# trinamic-controller.net
KiCad netlist of a schematic drawn in Altium Designer
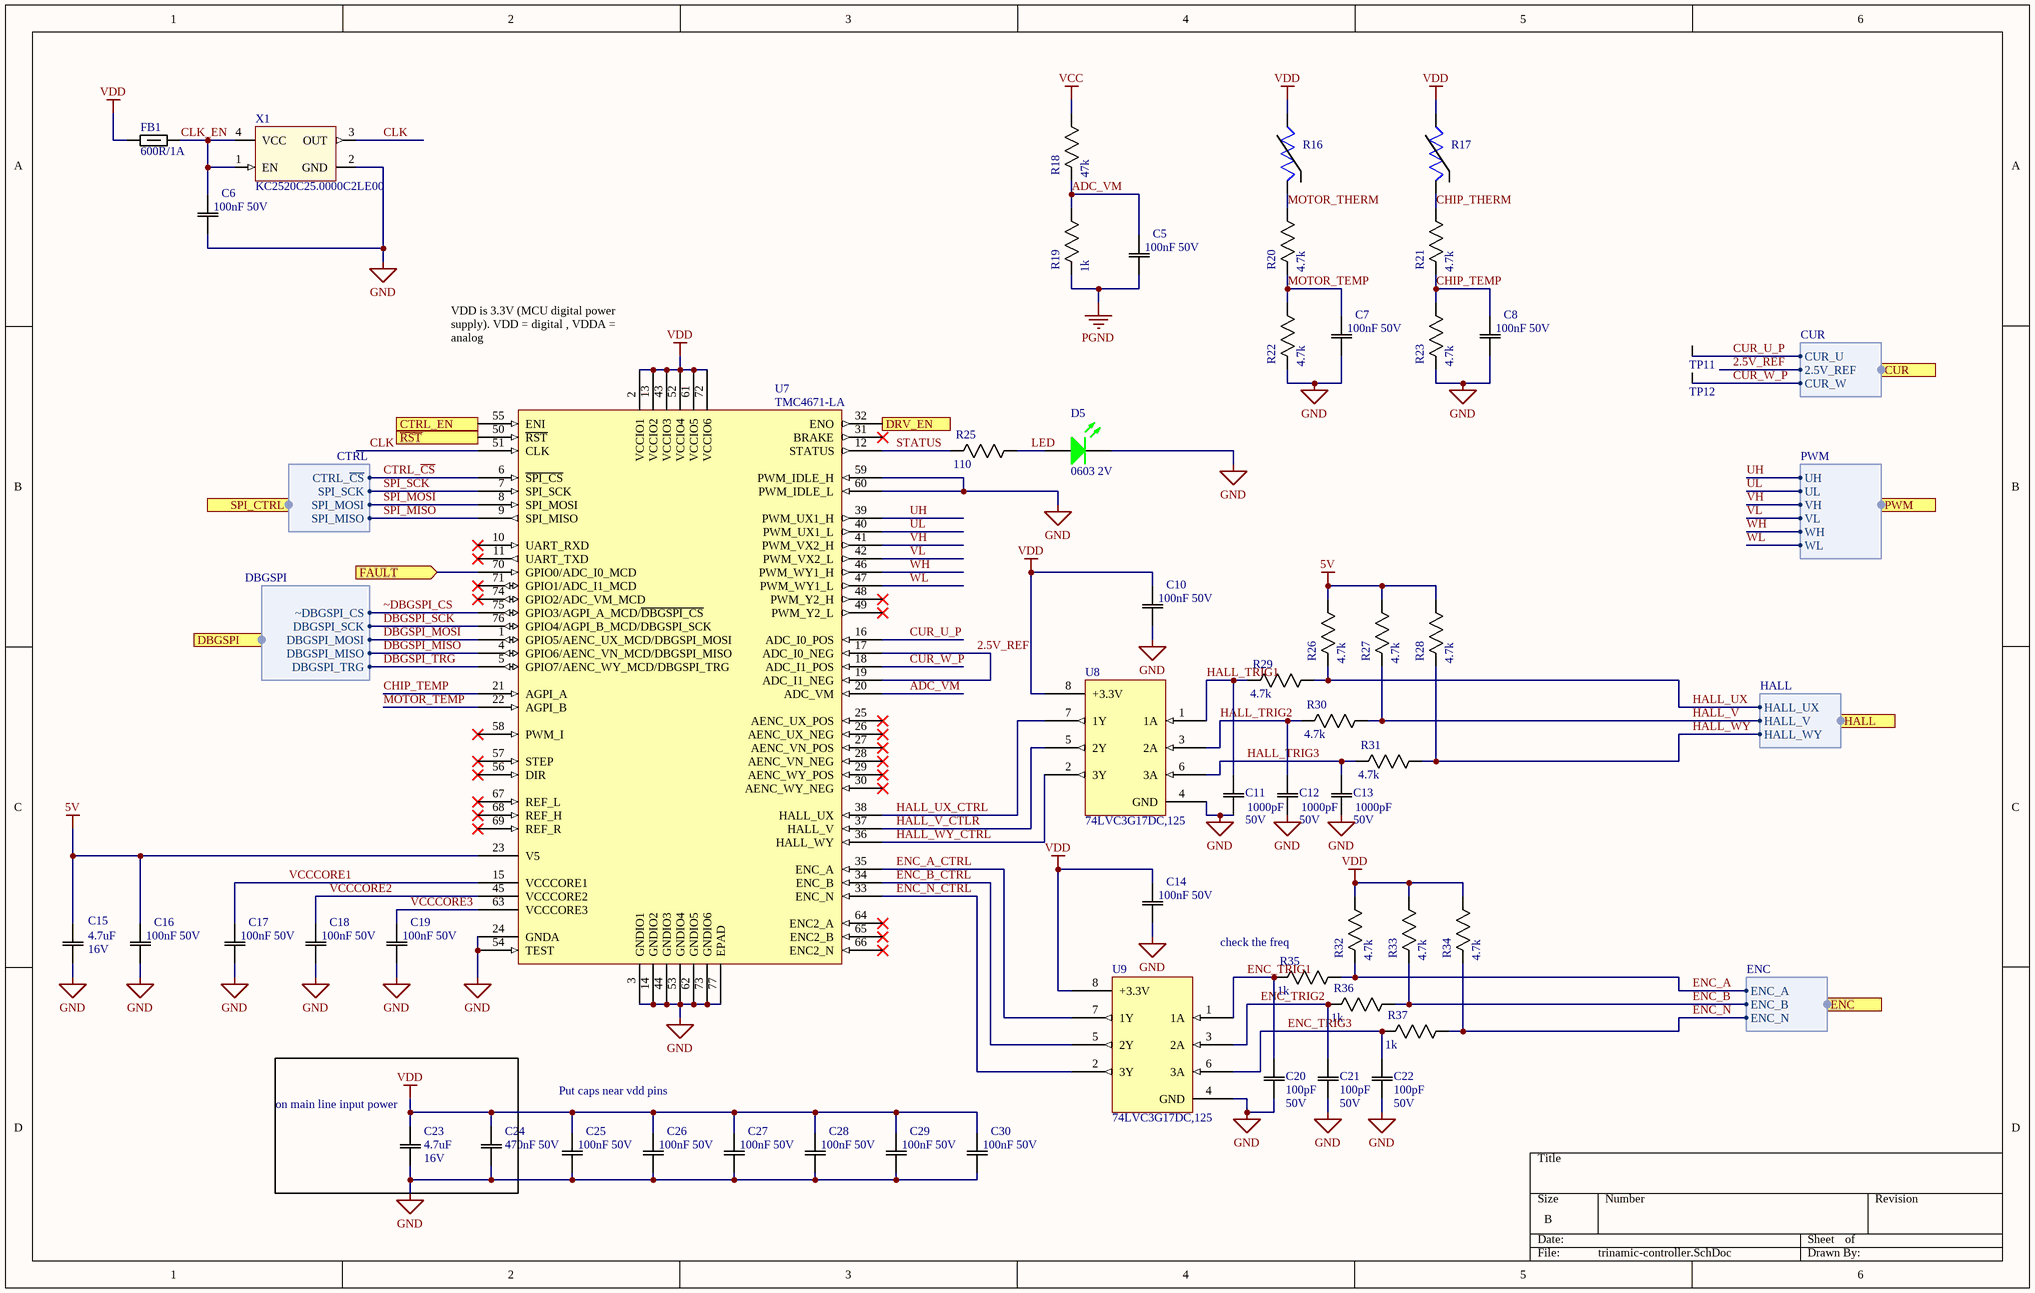
[diagram p0: trinamic-controller.SchDoc]

(export (version "E")
  (design (tool "Eeschema 10.0.6"))
  (components
    (comp (ref "C5")
      (value "100nF 50V")
      (footprint "0603")
      (description "Default Symbol for Capacitors")
      (fields (field (name "TOLERANCE") "10%") (field (name "PART NUMBER") "CAP 100nF 50V"))
      (libsource (lib "capacitor_library") (part "CAP_Default"))
    )
    (comp (ref "C6")
      (value "100nF 50V")
      (footprint "0603")
      (description "Default Symbol for Capacitors")
      (fields (field (name "TOLERANCE") "10%") (field (name "PART NUMBER") "CAP 100nF 50V"))
      (libsource (lib "capacitor_library") (part "CAP_Default"))
    )
    (comp (ref "C7")
      (value "100nF 50V")
      (footprint "0603")
      (description "Default Symbol for Capacitors")
      (fields (field (name "TOLERANCE") "10%") (field (name "PART NUMBER") "CAP 100nF 50V"))
      (libsource (lib "capacitor_library") (part "CAP_Default"))
    )
    (comp (ref "C8")
      (value "100nF 50V")
      (footprint "0603")
      (description "Default Symbol for Capacitors")
      (fields (field (name "TOLERANCE") "10%") (field (name "PART NUMBER") "CAP 100nF 50V"))
      (libsource (lib "capacitor_library") (part "CAP_Default"))
    )
    (comp (ref "C10")
      (value "100nF 50V")
      (footprint "0603")
      (description "Default Symbol for Capacitors")
      (fields (field (name "TOLERANCE") "10%") (field (name "PART NUMBER") "CAP 100nF 50V"))
      (libsource (lib "capacitor_library") (part "CAP_Default"))
    )
    (comp (ref "C11")
      (value "1000pF")
      (footprint "0603")
      (description "Default Symbol for Capacitors")
      (fields
        (field (name "TOLERANCE") "10%")
        (field (name "RATING") "50V")
        (field (name "PART NUMBER") "CAP 1000pF 50V")
      )
      (libsource (lib "capacitor_library") (part "CAP_Default"))
    )
    (comp (ref "C12")
      (value "1000pF")
      (footprint "0603")
      (description "Default Symbol for Capacitors")
      (fields
        (field (name "TOLERANCE") "10%")
        (field (name "RATING") "50V")
        (field (name "PART NUMBER") "CAP 1000pF 50V")
      )
      (libsource (lib "capacitor_library") (part "CAP_Default"))
    )
    (comp (ref "C13")
      (value "1000pF")
      (footprint "0603")
      (description "Default Symbol for Capacitors")
      (fields
        (field (name "TOLERANCE") "10%")
        (field (name "RATING") "50V")
        (field (name "PART NUMBER") "CAP 1000pF 50V")
      )
      (libsource (lib "capacitor_library") (part "CAP_Default"))
    )
    (comp (ref "C14")
      (value "100nF 50V")
      (footprint "0603")
      (description "Default Symbol for Capacitors")
      (fields (field (name "TOLERANCE") "10%") (field (name "PART NUMBER") "CAP 100nF 50V"))
      (libsource (lib "capacitor_library") (part "CAP_Default"))
    )
    (comp (ref "C15")
      (value "4.7uF")
      (footprint "0603")
      (description "Default Symbol for Capacitors")
      (fields
        (field (name "TOLERANCE") "10%")
        (field (name "RATING") "16V")
        (field (name "PART NUMBER") "CAP 4.7uF 16V")
      )
      (libsource (lib "capacitor_library") (part "CAP_Default"))
    )
    (comp (ref "C16")
      (value "100nF 50V")
      (footprint "0603")
      (description "Default Symbol for Capacitors")
      (fields (field (name "TOLERANCE") "10%") (field (name "PART NUMBER") "CAP 100nF 50V"))
      (libsource (lib "capacitor_library") (part "CAP_Default"))
    )
    (comp (ref "C17")
      (value "100nF 50V")
      (footprint "0603")
      (description "Default Symbol for Capacitors")
      (fields (field (name "TOLERANCE") "10%") (field (name "PART NUMBER") "CAP 100nF 50V"))
      (libsource (lib "capacitor_library") (part "CAP_Default"))
    )
    (comp (ref "C18")
      (value "100nF 50V")
      (footprint "0603")
      (description "Default Symbol for Capacitors")
      (fields (field (name "TOLERANCE") "10%") (field (name "PART NUMBER") "CAP 100nF 50V"))
      (libsource (lib "capacitor_library") (part "CAP_Default"))
    )
    (comp (ref "C19")
      (value "100nF 50V")
      (footprint "0603")
      (description "Default Symbol for Capacitors")
      (fields (field (name "TOLERANCE") "10%") (field (name "PART NUMBER") "CAP 100nF 50V"))
      (libsource (lib "capacitor_library") (part "CAP_Default"))
    )
    (comp (ref "C20")
      (value "100pF")
      (footprint "0603")
      (description "Default Symbol for Capacitors")
      (fields
        (field (name "TOLERANCE") "10%")
        (field (name "RATING") "50V")
        (field (name "PART NUMBER") "CAP 100pF 50V")
      )
      (libsource (lib "capacitor_library") (part "CAP_Default"))
    )
    (comp (ref "C21")
      (value "100pF")
      (footprint "0603")
      (description "Default Symbol for Capacitors")
      (fields
        (field (name "TOLERANCE") "10%")
        (field (name "RATING") "50V")
        (field (name "PART NUMBER") "CAP 100pF 50V")
      )
      (libsource (lib "capacitor_library") (part "CAP_Default"))
    )
    (comp (ref "C22")
      (value "100pF")
      (footprint "0603")
      (description "Default Symbol for Capacitors")
      (fields
        (field (name "TOLERANCE") "10%")
        (field (name "RATING") "50V")
        (field (name "PART NUMBER") "CAP 100pF 50V")
      )
      (libsource (lib "capacitor_library") (part "CAP_Default"))
    )
    (comp (ref "C23")
      (value "4.7uF")
      (footprint "0603")
      (description "Default Symbol for Capacitors")
      (fields
        (field (name "TOLERANCE") "10%")
        (field (name "RATING") "16V")
        (field (name "PART NUMBER") "CAP 4.7uF 16V")
      )
      (libsource (lib "capacitor_library") (part "CAP_Default"))
    )
    (comp (ref "C24")
      (value "470nF 50V")
      (footprint "0603")
      (description "Default Symbol for Capacitors")
      (fields (field (name "TOLERANCE") "10%") (field (name "PART NUMBER") "CAP 470nF 50V"))
      (libsource (lib "capacitor_library") (part "CAP_Default"))
    )
    (comp (ref "C25")
      (value "100nF 50V")
      (footprint "0603")
      (description "Default Symbol for Capacitors")
      (fields (field (name "TOLERANCE") "10%") (field (name "PART NUMBER") "CAP 100nF 50V"))
      (libsource (lib "capacitor_library") (part "CAP_Default"))
    )
    (comp (ref "C26")
      (value "100nF 50V")
      (footprint "0603")
      (description "Default Symbol for Capacitors")
      (fields (field (name "TOLERANCE") "10%") (field (name "PART NUMBER") "CAP 100nF 50V"))
      (libsource (lib "capacitor_library") (part "CAP_Default"))
    )
    (comp (ref "C27")
      (value "100nF 50V")
      (footprint "0603")
      (description "Default Symbol for Capacitors")
      (fields (field (name "TOLERANCE") "10%") (field (name "PART NUMBER") "CAP 100nF 50V"))
      (libsource (lib "capacitor_library") (part "CAP_Default"))
    )
    (comp (ref "C28")
      (value "100nF 50V")
      (footprint "0603")
      (description "Default Symbol for Capacitors")
      (fields (field (name "TOLERANCE") "10%") (field (name "PART NUMBER") "CAP 100nF 50V"))
      (libsource (lib "capacitor_library") (part "CAP_Default"))
    )
    (comp (ref "C29")
      (value "100nF 50V")
      (footprint "0603")
      (description "Default Symbol for Capacitors")
      (fields (field (name "TOLERANCE") "10%") (field (name "PART NUMBER") "CAP 100nF 50V"))
      (libsource (lib "capacitor_library") (part "CAP_Default"))
    )
    (comp (ref "C30")
      (value "100nF 50V")
      (footprint "0603")
      (description "Default Symbol for Capacitors")
      (fields (field (name "TOLERANCE") "10%") (field (name "PART NUMBER") "CAP 100nF 50V"))
      (libsource (lib "capacitor_library") (part "CAP_Default"))
    )
    (comp (ref "D5")
      (value "0603 2V")
      (footprint "0603 - LED")
      (description "LED Uni-Color Green 574nm 2-Pin Chip LED T/R")
      (fields (field (name "PART NUMBER") "LED GREEN SMD 0603"))
      (libsource (lib "Diode_Library") (part "LED GREEN SMD 0603"))
    )
    (comp (ref "FB1")
      (value "600R/1A")
      (footprint "0603")
      (fields (field (name "PART NUMBER") "FERRITE BEAD 200 MOHM 0603 1LN"))
      (libsource (lib "Inductor_Library") (part "FERRITE BEAD 200 MOHM 0603 1LN"))
    )
    (comp (ref "R16")
      (value "RES NTC 10k")
      (footprint "THERMISTOR TH")
      (fields (field (name "PART NUMBER") "RES NTC 10k TH") (field (name "TOLERANCE") "1%"))
      (libsource (lib "Resistor_Library") (part "RES NTC 10k"))
    )
    (comp (ref "R17")
      (value "RES NTC 10k")
      (footprint "0603")
      (fields (field (name "PART NUMBER") "RES NTC 10k CHIP") (field (name "TOLERANCE") "1%"))
      (libsource (lib "Resistor_Library") (part "RES NTC 10k"))
    )
    (comp (ref "R18")
      (value "47k")
      (footprint "0603")
      (description "Default Resistor Symbol")
      (fields (field (name "TOLERANCE") "1%") (field (name "PART NUMBER") "RES 47k 1/8W - 1%"))
      (libsource (lib "Resistor_Library") (part "RES_DEFAULT"))
    )
    (comp (ref "R19")
      (value "1k")
      (footprint "0603")
      (description "Default Resistor Symbol")
      (fields (field (name "TOLERANCE") "1%") (field (name "PART NUMBER") "RES 1k 1/8W - 1%"))
      (libsource (lib "") (part "RES_DEFAULT_1"))
    )
    (comp (ref "R20")
      (value "4.7k")
      (footprint "0603")
      (description "Default Resistor Symbol")
      (fields (field (name "TOLERANCE") "1%") (field (name "PART NUMBER") "RES 4.7k 1/8W - 1%"))
      (libsource (lib "Resistor_Library") (part "RES_DEFAULT"))
    )
    (comp (ref "R21")
      (value "4.7k")
      (footprint "0603")
      (description "Default Resistor Symbol")
      (fields (field (name "TOLERANCE") "1%") (field (name "PART NUMBER") "RES 4.7k 1/8W - 1%"))
      (libsource (lib "Resistor_Library") (part "RES_DEFAULT"))
    )
    (comp (ref "R22")
      (value "4.7k")
      (footprint "0603")
      (description "Default Resistor Symbol")
      (fields (field (name "TOLERANCE") "1%") (field (name "PART NUMBER") "RES 4.7k 1/8W - 1%"))
      (libsource (lib "Resistor_Library") (part "RES_DEFAULT"))
    )
    (comp (ref "R23")
      (value "4.7k")
      (footprint "0603")
      (description "Default Resistor Symbol")
      (fields (field (name "TOLERANCE") "1%") (field (name "PART NUMBER") "RES 4.7k 1/8W - 1%"))
      (libsource (lib "Resistor_Library") (part "RES_DEFAULT"))
    )
    (comp (ref "R25")
      (value "110")
      (footprint "0603")
      (description "Default Resistor Symbol")
      (fields (field (name "TOLERANCE") "1%") (field (name "PART NUMBER") "RES 110.0 1/8W - 1%"))
      (libsource (lib "") (part "RES_DEFAULT_1"))
    )
    (comp (ref "R26")
      (value "4.7k")
      (footprint "0603")
      (description "Default Resistor Symbol")
      (fields (field (name "TOLERANCE") "5%") (field (name "PART NUMBER") "RES 4.7k 1/8W - 5%"))
      (libsource (lib "") (part "RES_DEFAULT_1"))
    )
    (comp (ref "R27")
      (value "4.7k")
      (footprint "0603")
      (description "Default Resistor Symbol")
      (fields (field (name "TOLERANCE") "5%") (field (name "PART NUMBER") "RES 4.7k 1/8W - 5%"))
      (libsource (lib "") (part "RES_DEFAULT_1"))
    )
    (comp (ref "R28")
      (value "4.7k")
      (footprint "0603")
      (description "Default Resistor Symbol")
      (fields (field (name "TOLERANCE") "5%") (field (name "PART NUMBER") "RES 4.7k 1/8W - 5%"))
      (libsource (lib "Resistor_Library") (part "RES_DEFAULT"))
    )
    (comp (ref "R29")
      (value "4.7k")
      (footprint "0603")
      (description "Default Resistor Symbol")
      (fields (field (name "TOLERANCE") "5%") (field (name "PART NUMBER") "RES 4.7k 1/8W - 5%"))
      (libsource (lib "") (part "RES_DEFAULT_1"))
    )
    (comp (ref "R30")
      (value "4.7k")
      (footprint "0603")
      (description "Default Resistor Symbol")
      (fields (field (name "TOLERANCE") "5%") (field (name "PART NUMBER") "RES 4.7k 1/8W - 5%"))
      (libsource (lib "") (part "RES_DEFAULT_1"))
    )
    (comp (ref "R31")
      (value "4.7k")
      (footprint "0603")
      (description "Default Resistor Symbol")
      (fields (field (name "TOLERANCE") "5%") (field (name "PART NUMBER") "RES 4.7k 1/8W - 5%"))
      (libsource (lib "") (part "RES_DEFAULT_1"))
    )
    (comp (ref "R32")
      (value "4.7k")
      (footprint "0603")
      (description "Default Resistor Symbol")
      (fields (field (name "TOLERANCE") "5%") (field (name "PART NUMBER") "RES 4.7k 1/8W - 5%"))
      (libsource (lib "") (part "RES_DEFAULT_1"))
    )
    (comp (ref "R33")
      (value "4.7k")
      (footprint "0603")
      (description "Default Resistor Symbol")
      (fields (field (name "TOLERANCE") "5%") (field (name "PART NUMBER") "RES 4.7k 1/8W - 5%"))
      (libsource (lib "") (part "RES_DEFAULT_1"))
    )
    (comp (ref "R34")
      (value "4.7k")
      (footprint "0603")
      (description "Default Resistor Symbol")
      (fields (field (name "TOLERANCE") "5%") (field (name "PART NUMBER") "RES 4.7k 1/8W - 5%"))
      (libsource (lib "Resistor_Library") (part "RES_DEFAULT"))
    )
    (comp (ref "R35")
      (value "1k")
      (footprint "0603")
      (description "Default Resistor Symbol")
      (fields (field (name "TOLERANCE") "1%") (field (name "PART NUMBER") "RES 1k 1/8W - 1%"))
      (libsource (lib "Resistor_Library") (part "RES_DEFAULT"))
    )
    (comp (ref "R36")
      (value "1k")
      (footprint "0603")
      (description "Default Resistor Symbol")
      (fields (field (name "TOLERANCE") "1%") (field (name "PART NUMBER") "RES 1k 1/8W - 1%"))
      (libsource (lib "") (part "RES_DEFAULT_1"))
    )
    (comp (ref "R37")
      (value "1k")
      (footprint "0603")
      (description "Default Resistor Symbol")
      (fields (field (name "TOLERANCE") "1%") (field (name "PART NUMBER") "RES 1k 1/8W - 1%"))
      (libsource (lib "Resistor_Library") (part "RES_DEFAULT"))
    )
    (comp (ref "TP11")
      (value "C_U")
      (footprint "TP")
      (fields (field (name "PART NUMBER") "Test Point (Via)"))
      (libsource (lib "IC_Library") (part "Test Point (Via)"))
    )
    (comp (ref "TP12")
      (value "C_W")
      (footprint "TP")
      (fields (field (name "PART NUMBER") "Test Point (Via)"))
      (libsource (lib "IC_Library") (part "Test Point (Via)"))
    )
    (comp (ref "U7")
      (value "TMC4671-LA")
      (footprint "QFN40P1050X650X90_HS-77N")
      (description "Motor Driver, -40 To 125Deg C Rohs Compliant: Yes")
      (fields (field (name "PART NUMBER") "TMC4671"))
      (libsource (lib "IC_Library") (part "TMC4671"))
    )
    (comp (ref "U8")
      (value "74LVC3G17DC,125")
      (footprint "8-VSSOP")
      (description "IC BUFFER TRIPLE SCHMITT TRIGGER 5.5V VSSOP-8")
      (fields (field (name "PART NUMBER") "IC 74LVC3G17DC,125"))
      (libsource (lib "IC_Library") (part "IC 74LVC3G17DC,125"))
    )
    (comp (ref "U9")
      (value "74LVC3G17DC,125")
      (footprint "8-VSSOP")
      (description "IC BUFFER TRIPLE SCHMITT TRIGGER 5.5V VSSOP-8")
      (fields (field (name "PART NUMBER") "IC 74LVC3G17DC,125"))
      (libsource (lib "IC_Library") (part "IC 74LVC3G17DC,125"))
    )
    (comp (ref "X1")
      (value "KC2520C25.0000C2LE00")
      (footprint "KC2520C25.0000C2LE00")
      (description "Oscillator XO 25MHz ±15ppm 15pF CMOS 55% 2.5V/3.3V 4-Pin Mini-CSMD T/R")
      (fields (field (name "PART NUMBER") "XTAL OSC 25MHz 3.3V"))
      (libsource (lib "Oscillator_Library") (part "XTAL OSC 25MHz 3.3V"))
    )
  )
  (nets
    (net (code "7") (name "/2.5V_REF") (class "Default")
      (node (ref "U7") (pin "17") (pinfunction "ADC_I0_NEG_17") (pintype "input"))
      (node (ref "U7") (pin "19") (pinfunction "ADC_I1_NEG_19") (pintype "input"))
    )
    (net (code "8") (name "/ADC_VM") (class "Default")
      (node (ref "C5") (pin "2") (pinfunction "C2_2") (pintype "passive"))
      (node (ref "R18") (pin "2") (pinfunction "R2_2") (pintype "passive"))
      (node (ref "R19") (pin "1") (pinfunction "R1_1") (pintype "passive"))
      (node (ref "U7") (pin "20") (pinfunction "ADC_VM_20") (pintype "input"))
    )
    (net (code "9") (name "/CHIP_TEMP") (class "Default")
      (node (ref "C8") (pin "2") (pinfunction "C2_2") (pintype "passive"))
      (node (ref "R21") (pin "2") (pinfunction "R2_2") (pintype "passive"))
      (node (ref "R23") (pin "1") (pinfunction "R1_1") (pintype "passive"))
      (node (ref "U7") (pin "21") (pinfunction "AGPI_A_21") (pintype "input"))
    )
    (net (code "10") (name "/CHIP_THERM") (class "Default")
      (node (ref "R17") (pin "1") (pinfunction "1_1") (pintype "passive"))
      (node (ref "R21") (pin "1") (pinfunction "R1_1") (pintype "passive"))
    )
    (net (code "11") (name "/CLK") (class "Default")
      (node (ref "U7") (pin "51") (pinfunction "CLK_51") (pintype "input"))
      (node (ref "X1") (pin "3") (pinfunction "OUT_3") (pintype "output"))
    )
    (net (code "12") (name "/CLK_EN") (class "Default")
      (node (ref "C6") (pin "2") (pinfunction "C2_2") (pintype "passive"))
      (node (ref "FB1") (pin "2") (pinfunction "2_2") (pintype "passive"))
      (node (ref "X1") (pin "1") (pinfunction "EN_1") (pintype "input"))
      (node (ref "X1") (pin "4") (pinfunction "VCC_4") (pintype "power_in"))
    )
    (net (code "13") (name "/CTRL_EN") (class "Default")
      (node (ref "U7") (pin "55") (pinfunction "ENI_55") (pintype "input"))
    )
    (net (code "14") (name "/CTRL_~{CS}") (class "Default")
      (node (ref "U7") (pin "6") (pinfunction "~{SPI_CS}_6") (pintype "input"))
    )
    (net (code "15") (name "/CUR_U_P") (class "Default")
      (node (ref "TP11") (pin "1") (pinfunction "1_1") (pintype "passive"))
      (node (ref "U7") (pin "16") (pinfunction "ADC_I0_POS_16") (pintype "input"))
    )
    (net (code "16") (name "/CUR_W_P") (class "Default")
      (node (ref "TP12") (pin "1") (pinfunction "1_1") (pintype "passive"))
      (node (ref "U7") (pin "18") (pinfunction "ADC_I1_POS_18") (pintype "input"))
    )
    (net (code "17") (name "/DBGSPI_MISO") (class "Default")
      (node (ref "U7") (pin "4") (pinfunction "GPIO6/AENC_VN_MCD/DBGSPI_MISO_4") (pintype "bidirectional"))
    )
    (net (code "18") (name "/DBGSPI_MOSI") (class "Default")
      (node (ref "U7") (pin "1") (pinfunction "GPIO5/AENC_UX_MCD/DBGSPI_MOSI_1") (pintype "bidirectional"))
    )
    (net (code "19") (name "/DBGSPI_SCK") (class "Default")
      (node (ref "U7") (pin "76") (pinfunction "GPIO4/AGPI_B_MCD/DBGSPI_SCK_76") (pintype "bidirectional"))
    )
    (net (code "20") (name "/DBGSPI_TRG") (class "Default")
      (node (ref "U7") (pin "5") (pinfunction "GPIO7/AENC_WY_MCD/DBGSPI_TRG_5") (pintype "bidirectional"))
    )
    (net (code "21") (name "/DRV_EN") (class "Default")
      (node (ref "U7") (pin "32") (pinfunction "ENO_32") (pintype "output"))
    )
    (net (code "22") (name "/ENC_A") (class "Default")
      (node (ref "R32") (pin "2") (pinfunction "R2_2") (pintype "passive"))
      (node (ref "R35") (pin "1") (pinfunction "R1_1") (pintype "passive"))
    )
    (net (code "23") (name "/ENC_A_CTRL") (class "Default")
      (node (ref "U7") (pin "35") (pinfunction "ENC_A_35") (pintype "input"))
      (node (ref "U9") (pin "7") (pinfunction "1Y_7") (pintype "output"))
    )
    (net (code "24") (name "/ENC_B") (class "Default")
      (node (ref "R33") (pin "2") (pinfunction "R2_2") (pintype "passive"))
      (node (ref "R36") (pin "1") (pinfunction "R1_1") (pintype "passive"))
    )
    (net (code "25") (name "/ENC_B_CTRL") (class "Default")
      (node (ref "U7") (pin "34") (pinfunction "ENC_B_34") (pintype "input"))
      (node (ref "U9") (pin "5") (pinfunction "2Y_5") (pintype "output"))
    )
    (net (code "26") (name "/ENC_N") (class "Default")
      (node (ref "R34") (pin "2") (pinfunction "R2_2") (pintype "passive"))
      (node (ref "R37") (pin "1") (pinfunction "R1_1") (pintype "passive"))
    )
    (net (code "27") (name "/ENC_N_CTRL") (class "Default")
      (node (ref "U7") (pin "33") (pinfunction "ENC_N_33") (pintype "input"))
      (node (ref "U9") (pin "2") (pinfunction "3Y_2") (pintype "output"))
    )
    (net (code "28") (name "/ENC_TRIG1") (class "Default")
      (node (ref "C20") (pin "2") (pinfunction "C2_2") (pintype "passive"))
      (node (ref "R35") (pin "2") (pinfunction "R2_2") (pintype "passive"))
      (node (ref "U9") (pin "1") (pinfunction "1A_1") (pintype "input"))
    )
    (net (code "29") (name "/ENC_TRIG2") (class "Default")
      (node (ref "C21") (pin "2") (pinfunction "C2_2") (pintype "passive"))
      (node (ref "R36") (pin "2") (pinfunction "R2_2") (pintype "passive"))
      (node (ref "U9") (pin "3") (pinfunction "2A_3") (pintype "input"))
    )
    (net (code "30") (name "/ENC_TRIG3") (class "Default")
      (node (ref "C22") (pin "2") (pinfunction "C2_2") (pintype "passive"))
      (node (ref "R37") (pin "2") (pinfunction "R2_2") (pintype "passive"))
      (node (ref "U9") (pin "6") (pinfunction "3A_6") (pintype "input"))
    )
    (net (code "31") (name "/FAULT") (class "Default")
      (node (ref "U7") (pin "70") (pinfunction "GPIO0/ADC_I0_MCD_70") (pintype "input"))
    )
    (net (code "32") (name "/HALL_TRIG1") (class "Default")
      (node (ref "C11") (pin "2") (pinfunction "C2_2") (pintype "passive"))
      (node (ref "R29") (pin "2") (pinfunction "R2_2") (pintype "passive"))
      (node (ref "U8") (pin "1") (pinfunction "1A_1") (pintype "input"))
    )
    (net (code "33") (name "/HALL_TRIG2") (class "Default")
      (node (ref "C12") (pin "2") (pinfunction "C2_2") (pintype "passive"))
      (node (ref "R30") (pin "2") (pinfunction "R2_2") (pintype "passive"))
      (node (ref "U8") (pin "3") (pinfunction "2A_3") (pintype "input"))
    )
    (net (code "34") (name "/HALL_TRIG3") (class "Default")
      (node (ref "C13") (pin "2") (pinfunction "C2_2") (pintype "passive"))
      (node (ref "R31") (pin "2") (pinfunction "R2_2") (pintype "passive"))
      (node (ref "U8") (pin "6") (pinfunction "3A_6") (pintype "input"))
    )
    (net (code "35") (name "/HALL_UX") (class "Default")
      (node (ref "R26") (pin "2") (pinfunction "R2_2") (pintype "passive"))
      (node (ref "R29") (pin "1") (pinfunction "R1_1") (pintype "passive"))
    )
    (net (code "36") (name "/HALL_UX_CTRL") (class "Default")
      (node (ref "U7") (pin "38") (pinfunction "HALL_UX_38") (pintype "input"))
      (node (ref "U8") (pin "7") (pinfunction "1Y_7") (pintype "output"))
    )
    (net (code "37") (name "/HALL_V") (class "Default")
      (node (ref "R27") (pin "2") (pinfunction "R2_2") (pintype "passive"))
      (node (ref "R30") (pin "1") (pinfunction "R1_1") (pintype "passive"))
    )
    (net (code "38") (name "/HALL_V_CTLR") (class "Default")
      (node (ref "U7") (pin "37") (pinfunction "HALL_V_37") (pintype "input"))
      (node (ref "U8") (pin "5") (pinfunction "2Y_5") (pintype "output"))
    )
    (net (code "39") (name "/HALL_WY") (class "Default")
      (node (ref "R28") (pin "2") (pinfunction "R2_2") (pintype "passive"))
      (node (ref "R31") (pin "1") (pinfunction "R1_1") (pintype "passive"))
    )
    (net (code "40") (name "/HALL_WY_CTRL") (class "Default")
      (node (ref "U7") (pin "36") (pinfunction "HALL_WY_36") (pintype "input"))
      (node (ref "U8") (pin "2") (pinfunction "3Y_2") (pintype "output"))
    )
    (net (code "41") (name "/LED") (class "Default")
      (node (ref "D5") (pin "1") (pinfunction "A_1") (pintype "passive"))
      (node (ref "R25") (pin "1") (pinfunction "R1_1") (pintype "passive"))
    )
    (net (code "42") (name "/MOTOR_TEMP") (class "Default")
      (node (ref "C7") (pin "2") (pinfunction "C2_2") (pintype "passive"))
      (node (ref "R20") (pin "2") (pinfunction "R2_2") (pintype "passive"))
      (node (ref "R22") (pin "1") (pinfunction "R1_1") (pintype "passive"))
      (node (ref "U7") (pin "22") (pinfunction "AGPI_B_22") (pintype "input"))
    )
    (net (code "43") (name "/MOTOR_THERM") (class "Default")
      (node (ref "R16") (pin "1") (pinfunction "1_1") (pintype "passive"))
      (node (ref "R20") (pin "1") (pinfunction "R1_1") (pintype "passive"))
    )
    (net (code "44") (name "/SPI_MISO") (class "Default")
      (node (ref "U7") (pin "9") (pinfunction "SPI_MISO_9") (pintype "output"))
    )
    (net (code "45") (name "/SPI_MOSI") (class "Default")
      (node (ref "U7") (pin "8") (pinfunction "SPI_MOSI_8") (pintype "input"))
    )
    (net (code "46") (name "/SPI_SCK") (class "Default")
      (node (ref "U7") (pin "7") (pinfunction "SPI_SCK_7") (pintype "input"))
    )
    (net (code "47") (name "/STATUS") (class "Default")
      (node (ref "R25") (pin "2") (pinfunction "R2_2") (pintype "passive"))
      (node (ref "U7") (pin "12") (pinfunction "STATUS_12") (pintype "output"))
    )
    (net (code "48") (name "/UH") (class "Default")
      (node (ref "U7") (pin "39") (pinfunction "PWM_UX1_H_39") (pintype "output"))
    )
    (net (code "49") (name "/UL") (class "Default")
      (node (ref "U7") (pin "40") (pinfunction "PWM_UX1_L_40") (pintype "output"))
    )
    (net (code "50") (name "/VCCCORE1") (class "Default")
      (node (ref "C17") (pin "2") (pinfunction "C2_2") (pintype "passive"))
      (node (ref "U7") (pin "15") (pinfunction "VCCCORE1_15") (pintype "power_in"))
    )
    (net (code "51") (name "/VCCCORE2") (class "Default")
      (node (ref "C18") (pin "2") (pinfunction "C2_2") (pintype "passive"))
      (node (ref "U7") (pin "45") (pinfunction "VCCCORE2_45") (pintype "power_in"))
    )
    (net (code "52") (name "/VCCCORE3") (class "Default")
      (node (ref "C19") (pin "2") (pinfunction "C2_2") (pintype "passive"))
      (node (ref "U7") (pin "63") (pinfunction "VCCCORE3_63") (pintype "power_in"))
    )
    (net (code "53") (name "/VH") (class "Default")
      (node (ref "U7") (pin "41") (pinfunction "PWM_VX2_H_41") (pintype "output"))
    )
    (net (code "54") (name "/VL") (class "Default")
      (node (ref "U7") (pin "42") (pinfunction "PWM_VX2_L_42") (pintype "output"))
    )
    (net (code "55") (name "/WH") (class "Default")
      (node (ref "U7") (pin "46") (pinfunction "PWM_WY1_H_46") (pintype "output"))
    )
    (net (code "56") (name "/WL") (class "Default")
      (node (ref "U7") (pin "47") (pinfunction "PWM_WY1_L_47") (pintype "output"))
    )
    (net (code "63") (name "/~DBGSPI_CS") (class "Default")
      (node (ref "U7") (pin "75") (pinfunction "GPIO3/AGPI_A_MCD/~{DBGSPI_CS}_75") (pintype "bidirectional"))
    )
    (net (code "64") (name "/~{RST}") (class "Default")
      (node (ref "U7") (pin "50") (pinfunction "~{RST}_50") (pintype "input"))
    )
    (net (code "65") (name "5V") (class "Default")
      (node (ref "C15") (pin "2") (pinfunction "C2_2") (pintype "passive"))
      (node (ref "C16") (pin "2") (pinfunction "C2_2") (pintype "passive"))
      (node (ref "R26") (pin "1") (pinfunction "R1_1") (pintype "passive"))
      (node (ref "R27") (pin "1") (pinfunction "R1_1") (pintype "passive"))
      (node (ref "R28") (pin "1") (pinfunction "R1_1") (pintype "passive"))
      (node (ref "U7") (pin "23") (pinfunction "V5_23") (pintype "power_in"))
    )
    (net (code "66") (name "GND") (class "Default")
      (node (ref "C10") (pin "1") (pinfunction "C1_1") (pintype "passive"))
      (node (ref "C11") (pin "1") (pinfunction "C1_1") (pintype "passive"))
      (node (ref "C12") (pin "1") (pinfunction "C1_1") (pintype "passive"))
      (node (ref "C13") (pin "1") (pinfunction "C1_1") (pintype "passive"))
      (node (ref "C14") (pin "1") (pinfunction "C1_1") (pintype "passive"))
      (node (ref "C15") (pin "1") (pinfunction "C1_1") (pintype "passive"))
      (node (ref "C16") (pin "1") (pinfunction "C1_1") (pintype "passive"))
      (node (ref "C17") (pin "1") (pinfunction "C1_1") (pintype "passive"))
      (node (ref "C18") (pin "1") (pinfunction "C1_1") (pintype "passive"))
      (node (ref "C19") (pin "1") (pinfunction "C1_1") (pintype "passive"))
      (node (ref "C20") (pin "1") (pinfunction "C1_1") (pintype "passive"))
      (node (ref "C21") (pin "1") (pinfunction "C1_1") (pintype "passive"))
      (node (ref "C22") (pin "1") (pinfunction "C1_1") (pintype "passive"))
      (node (ref "C23") (pin "1") (pinfunction "C1_1") (pintype "passive"))
      (node (ref "C24") (pin "1") (pinfunction "C1_1") (pintype "passive"))
      (node (ref "C25") (pin "1") (pinfunction "C1_1") (pintype "passive"))
      (node (ref "C26") (pin "1") (pinfunction "C1_1") (pintype "passive"))
      (node (ref "C27") (pin "1") (pinfunction "C1_1") (pintype "passive"))
      (node (ref "C28") (pin "1") (pinfunction "C1_1") (pintype "passive"))
      (node (ref "C29") (pin "1") (pinfunction "C1_1") (pintype "passive"))
      (node (ref "C30") (pin "1") (pinfunction "C1_1") (pintype "passive"))
      (node (ref "C6") (pin "1") (pinfunction "C1_1") (pintype "passive"))
      (node (ref "C7") (pin "1") (pinfunction "C1_1") (pintype "passive"))
      (node (ref "C8") (pin "1") (pinfunction "C1_1") (pintype "passive"))
      (node (ref "D5") (pin "2") (pinfunction "K_2") (pintype "passive"))
      (node (ref "R22") (pin "2") (pinfunction "R2_2") (pintype "passive"))
      (node (ref "R23") (pin "2") (pinfunction "R2_2") (pintype "passive"))
      (node (ref "U7") (pin "14") (pinfunction "GNDIO2_14") (pintype "power_in"))
      (node (ref "U7") (pin "24") (pinfunction "GNDA_24") (pintype "power_in"))
      (node (ref "U7") (pin "3") (pinfunction "GNDIO1_3") (pintype "power_in"))
      (node (ref "U7") (pin "44") (pinfunction "GNDIO3_44") (pintype "power_in"))
      (node (ref "U7") (pin "53") (pinfunction "GNDIO4_53") (pintype "power_in"))
      (node (ref "U7") (pin "54") (pinfunction "TEST_54") (pintype "input"))
      (node (ref "U7") (pin "59") (pinfunction "PWM_IDLE_H_59") (pintype "input"))
      (node (ref "U7") (pin "60") (pinfunction "PWM_IDLE_L_60") (pintype "input"))
      (node (ref "U7") (pin "62") (pinfunction "GNDIO5_62") (pintype "power_in"))
      (node (ref "U7") (pin "73") (pinfunction "GNDIO6_73") (pintype "power_in"))
      (node (ref "U7") (pin "77") (pinfunction "EPAD_77") (pintype "passive"))
      (node (ref "U8") (pin "4") (pinfunction "GND_4") (pintype "power_in"))
      (node (ref "U9") (pin "4") (pinfunction "GND_4") (pintype "power_in"))
      (node (ref "X1") (pin "2") (pinfunction "GND_2") (pintype "power_in"))
    )
    (net (code "67") (name "PGND") (class "Default")
      (node (ref "C5") (pin "1") (pinfunction "C1_1") (pintype "passive"))
      (node (ref "R19") (pin "2") (pinfunction "R2_2") (pintype "passive"))
    )
    (net (code "68") (name "VCC") (class "Default")
      (node (ref "R18") (pin "1") (pinfunction "R1_1") (pintype "passive"))
    )
    (net (code "69") (name "VDD") (class "Default")
      (node (ref "C10") (pin "2") (pinfunction "C2_2") (pintype "passive"))
      (node (ref "C14") (pin "2") (pinfunction "C2_2") (pintype "passive"))
      (node (ref "C23") (pin "2") (pinfunction "C2_2") (pintype "passive"))
      (node (ref "C24") (pin "2") (pinfunction "C2_2") (pintype "passive"))
      (node (ref "C25") (pin "2") (pinfunction "C2_2") (pintype "passive"))
      (node (ref "C26") (pin "2") (pinfunction "C2_2") (pintype "passive"))
      (node (ref "C27") (pin "2") (pinfunction "C2_2") (pintype "passive"))
      (node (ref "C28") (pin "2") (pinfunction "C2_2") (pintype "passive"))
      (node (ref "C29") (pin "2") (pinfunction "C2_2") (pintype "passive"))
      (node (ref "C30") (pin "2") (pinfunction "C2_2") (pintype "passive"))
      (node (ref "FB1") (pin "1") (pinfunction "1_1") (pintype "passive"))
      (node (ref "R16") (pin "2") (pinfunction "2_2") (pintype "passive"))
      (node (ref "R17") (pin "2") (pinfunction "2_2") (pintype "passive"))
      (node (ref "R32") (pin "1") (pinfunction "R1_1") (pintype "passive"))
      (node (ref "R33") (pin "1") (pinfunction "R1_1") (pintype "passive"))
      (node (ref "R34") (pin "1") (pinfunction "R1_1") (pintype "passive"))
      (node (ref "U7") (pin "13") (pinfunction "VCCIO2_13") (pintype "power_in"))
      (node (ref "U7") (pin "2") (pinfunction "VCCIO1_2") (pintype "power_in"))
      (node (ref "U7") (pin "43") (pinfunction "VCCIO3_43") (pintype "power_in"))
      (node (ref "U7") (pin "52") (pinfunction "VCCIO4_52") (pintype "power_in"))
      (node (ref "U7") (pin "61") (pinfunction "VCCIO5_61") (pintype "power_in"))
      (node (ref "U7") (pin "72") (pinfunction "VCCIO6_72") (pintype "power_in"))
      (node (ref "U8") (pin "8") (pinfunction "+3.3V_8") (pintype "power_in"))
      (node (ref "U9") (pin "8") (pinfunction "+3.3V_8") (pintype "power_in"))
    )
    (net (code "70") (name "unconnected-(U7-AENC_UX_NEG-Pad26)") (class "Default")
      (node (ref "U7") (pin "26") (pinfunction "AENC_UX_NEG_26") (pintype "input+no_connect"))
    )
    (net (code "71") (name "unconnected-(U7-AENC_UX_POS-Pad25)") (class "Default")
      (node (ref "U7") (pin "25") (pinfunction "AENC_UX_POS_25") (pintype "input+no_connect"))
    )
    (net (code "72") (name "unconnected-(U7-AENC_VN_NEG-Pad28)") (class "Default")
      (node (ref "U7") (pin "28") (pinfunction "AENC_VN_NEG_28") (pintype "input+no_connect"))
    )
    (net (code "73") (name "unconnected-(U7-AENC_VN_POS-Pad27)") (class "Default")
      (node (ref "U7") (pin "27") (pinfunction "AENC_VN_POS_27") (pintype "input+no_connect"))
    )
    (net (code "74") (name "unconnected-(U7-AENC_WY_NEG-Pad30)") (class "Default")
      (node (ref "U7") (pin "30") (pinfunction "AENC_WY_NEG_30") (pintype "input+no_connect"))
    )
    (net (code "75") (name "unconnected-(U7-AENC_WY_POS-Pad29)") (class "Default")
      (node (ref "U7") (pin "29") (pinfunction "AENC_WY_POS_29") (pintype "input+no_connect"))
    )
    (net (code "76") (name "unconnected-(U7-BRAKE-Pad31)") (class "Default")
      (node (ref "U7") (pin "31") (pinfunction "BRAKE_31") (pintype "output+no_connect"))
    )
    (net (code "77") (name "unconnected-(U7-DIR-Pad56)") (class "Default")
      (node (ref "U7") (pin "56") (pinfunction "DIR_56") (pintype "input+no_connect"))
    )
    (net (code "78") (name "unconnected-(U7-ENC2_A-Pad64)") (class "Default")
      (node (ref "U7") (pin "64") (pinfunction "ENC2_A_64") (pintype "input+no_connect"))
    )
    (net (code "79") (name "unconnected-(U7-ENC2_B-Pad65)") (class "Default")
      (node (ref "U7") (pin "65") (pinfunction "ENC2_B_65") (pintype "input+no_connect"))
    )
    (net (code "80") (name "unconnected-(U7-ENC2_N-Pad66)") (class "Default")
      (node (ref "U7") (pin "66") (pinfunction "ENC2_N_66") (pintype "input+no_connect"))
    )
    (net (code "81") (name "unconnected-(U7-GPIO1{slash}ADC_I1_MCD-Pad71)") (class "Default")
      (node (ref "U7") (pin "71") (pinfunction "GPIO1/ADC_I1_MCD_71") (pintype "bidirectional+no_connect"))
    )
    (net (code "82") (name "unconnected-(U7-GPIO2{slash}ADC_VM_MCD-Pad74)") (class "Default")
      (node (ref "U7") (pin "74") (pinfunction "GPIO2/ADC_VM_MCD_74") (pintype "bidirectional+no_connect"))
    )
    (net (code "83") (name "unconnected-(U7-PWM_I-Pad58)") (class "Default")
      (node (ref "U7") (pin "58") (pinfunction "PWM_I_58") (pintype "input+no_connect"))
    )
    (net (code "84") (name "unconnected-(U7-PWM_Y2_H-Pad48)") (class "Default")
      (node (ref "U7") (pin "48") (pinfunction "PWM_Y2_H_48") (pintype "output+no_connect"))
    )
    (net (code "85") (name "unconnected-(U7-PWM_Y2_L-Pad49)") (class "Default")
      (node (ref "U7") (pin "49") (pinfunction "PWM_Y2_L_49") (pintype "output+no_connect"))
    )
    (net (code "86") (name "unconnected-(U7-REF_H-Pad68)") (class "Default")
      (node (ref "U7") (pin "68") (pinfunction "REF_H_68") (pintype "input+no_connect"))
    )
    (net (code "87") (name "unconnected-(U7-REF_L-Pad67)") (class "Default")
      (node (ref "U7") (pin "67") (pinfunction "REF_L_67") (pintype "input+no_connect"))
    )
    (net (code "88") (name "unconnected-(U7-REF_R-Pad69)") (class "Default")
      (node (ref "U7") (pin "69") (pinfunction "REF_R_69") (pintype "input+no_connect"))
    )
    (net (code "89") (name "unconnected-(U7-STEP-Pad57)") (class "Default")
      (node (ref "U7") (pin "57") (pinfunction "STEP_57") (pintype "input+no_connect"))
    )
    (net (code "90") (name "unconnected-(U7-UART_RXD-Pad10)") (class "Default")
      (node (ref "U7") (pin "10") (pinfunction "UART_RXD_10") (pintype "input+no_connect"))
    )
    (net (code "91") (name "unconnected-(U7-UART_TXD-Pad11)") (class "Default")
      (node (ref "U7") (pin "11") (pinfunction "UART_TXD_11") (pintype "output+no_connect"))
    )
  )
)
